# SCH_LoRaRice_Gateway__2024-06-10.net
KiCad netlist of a schematic drawn in EasyEDA
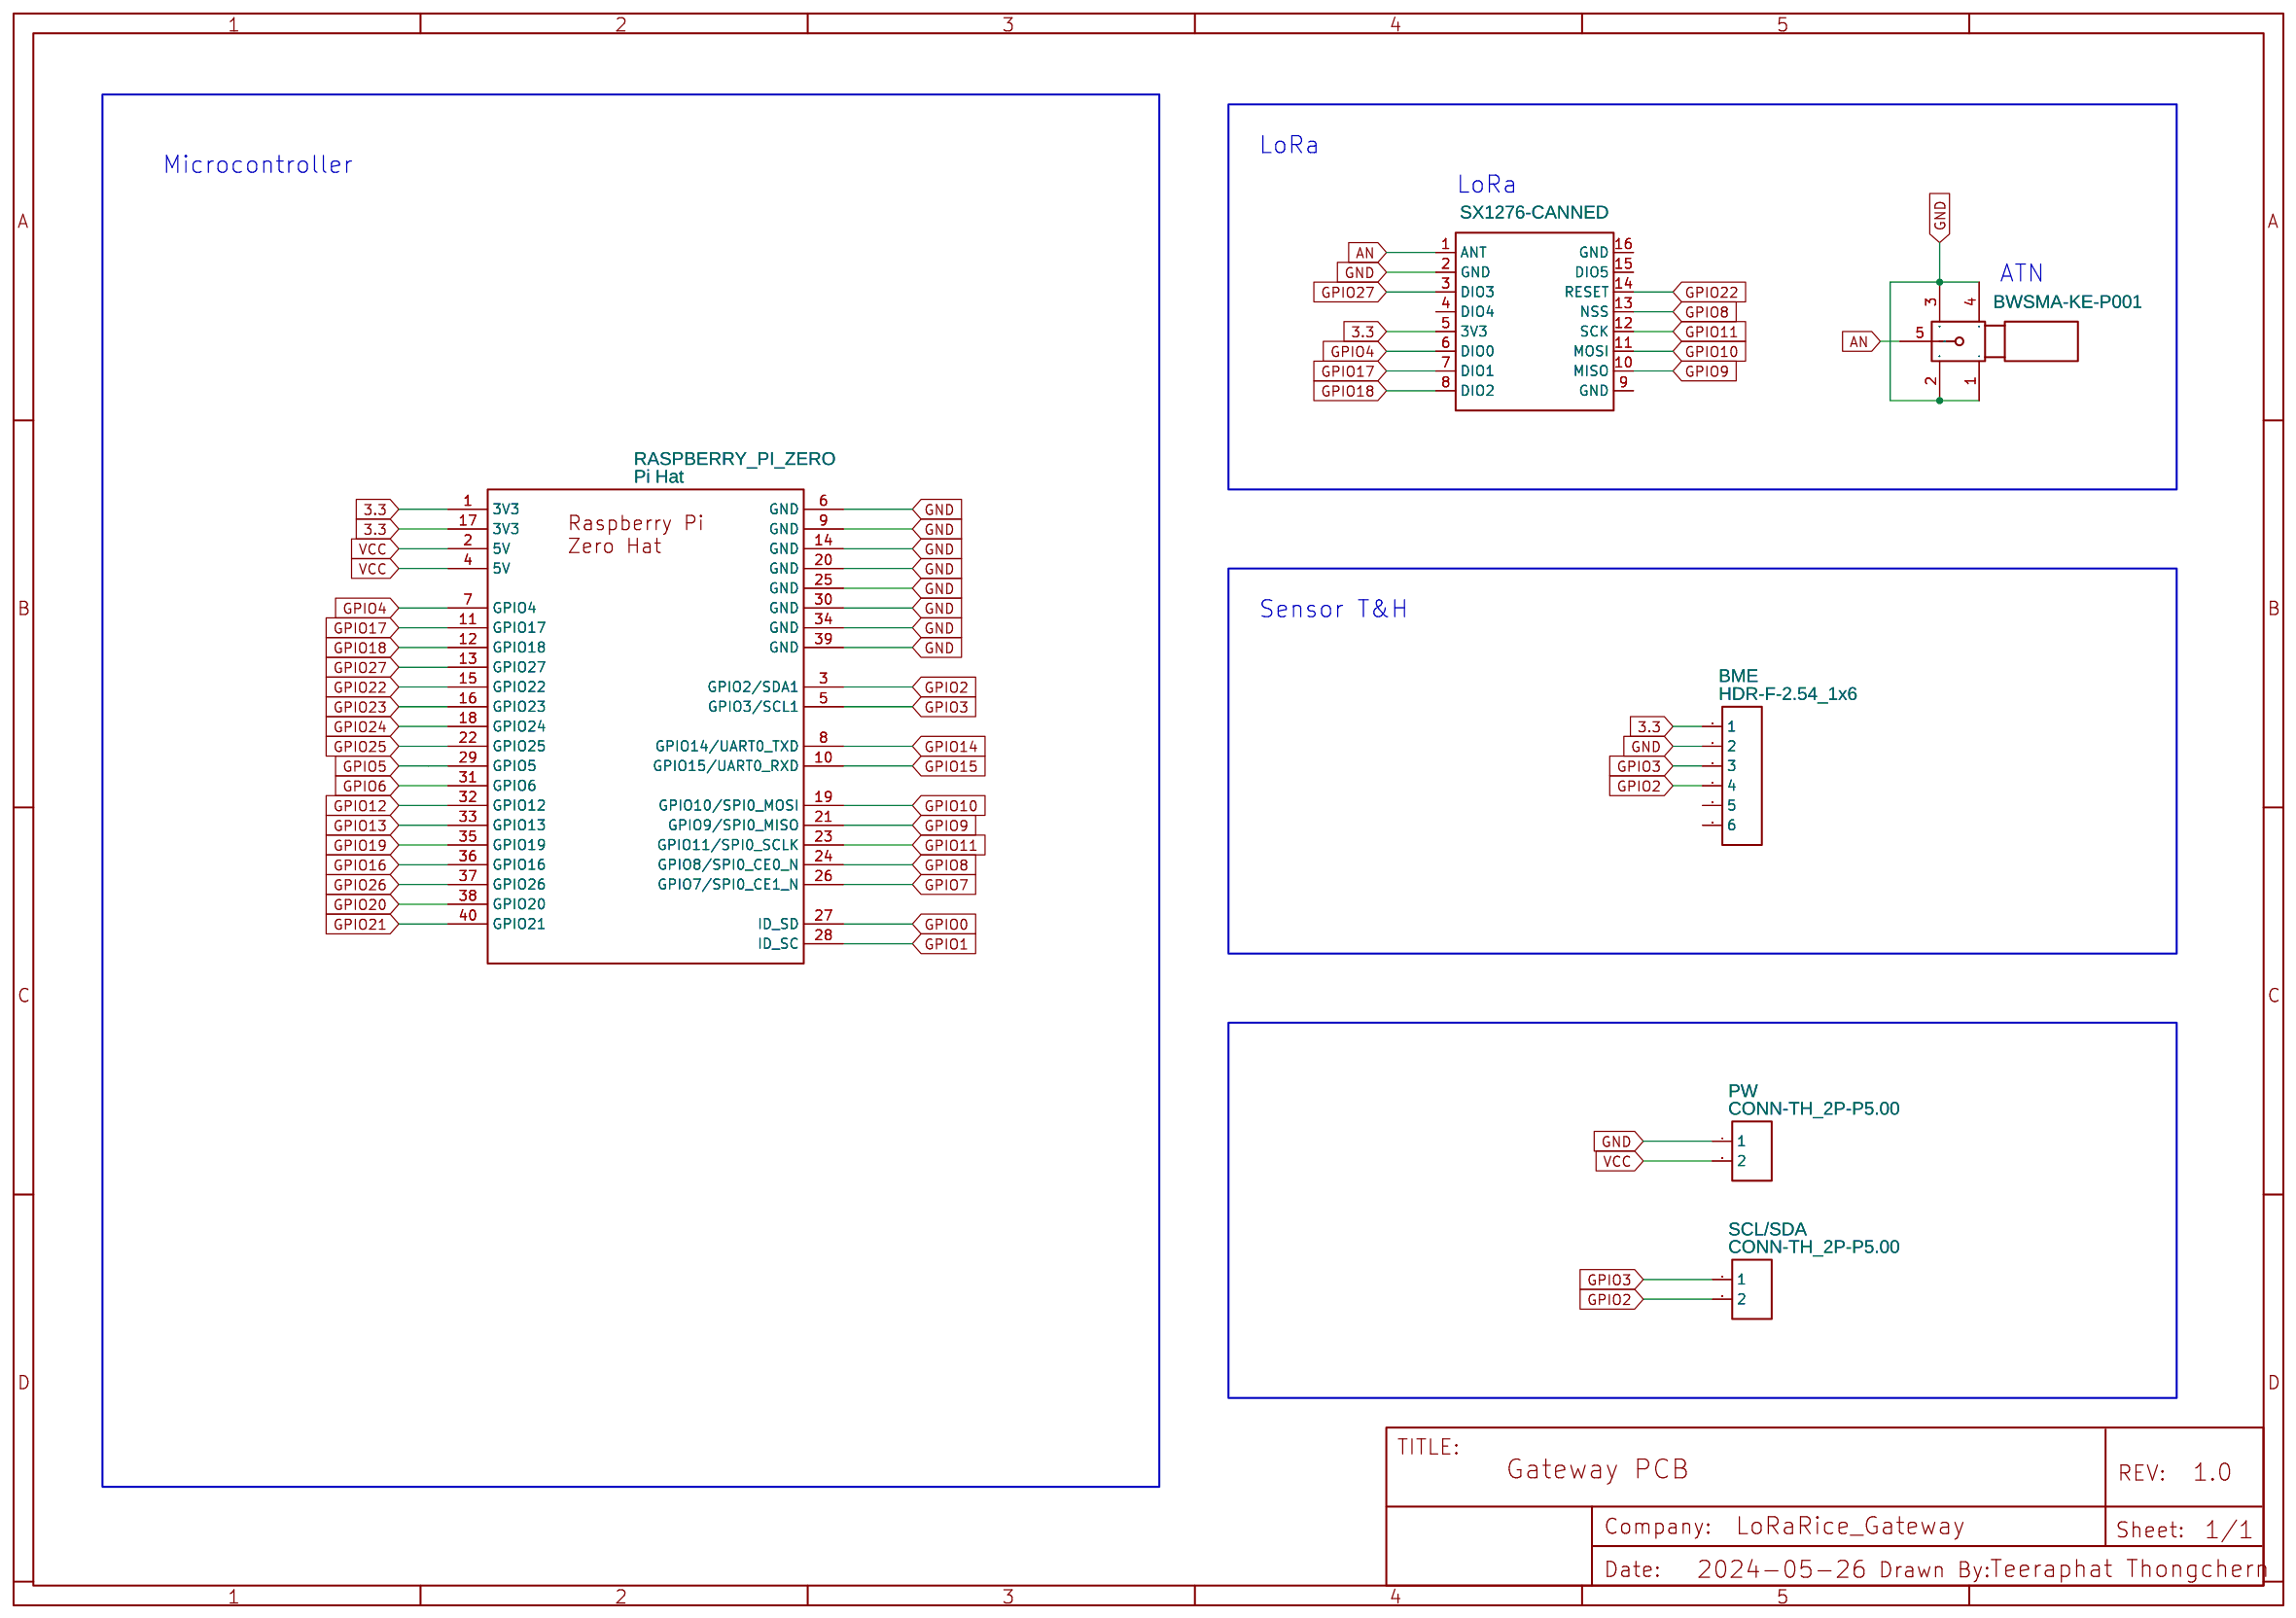
[diagram p0: schematic sheet]

(export (version "E")
  (design (tool "Eeschema 10.0.6"))
  (components
    (comp (ref "ATN")
      (value "BWSMA-KE-P001")
      (fields (field (name "Manufacturer") "BAT WIRELESS(蝙蝠无线)"))
      (libsource (lib "") (part "BWSMA-KE-P001"))
    )
    (comp (ref "BME") (value "HDR-F-2.54_1x6") (libsource (lib "") (part "HDR-F-2.54_1x6")))
    (comp (ref "LORA")
      (value "SX1276-CANNED")
      (fields (field (name "Manufacturer Part") "LoRa1276-C1") (field (name "Manufacturer") "G-NiceRF"))
      (libsource (lib "") (part "SX1276-CANNED"))
    )
    (comp (ref "PW") (value "CONN-TH_2P-P5.00") (libsource (lib "") (part "CONN-TH_2P-P5.00_1")))
    (comp (ref "RASPBERRY_PI_ZERO")
      (value "Pi Hat")
      (fields (field (name "Manufacturer") "Raspberry Pi Foundation"))
      (libsource (lib "") (part "RPI ZERO 2W"))
    )
    (comp (ref "SCL/SDA") (value "CONN-TH_2P-P5.00") (libsource (lib "") (part "CONN-TH_2P-P5.00")))
  )
  (nets
    (net (code "1") (name "3.3") (class "Default")
      (node (ref "BME") (pin "1") (pinfunction "1_1") (pintype "input"))
      (node (ref "LORA") (pin "5") (pinfunction "3V3_5") (pintype "unspecified"))
      (node (ref "RASPBERRY_PI_ZERO") (pin "1") (pinfunction "3V3_1") (pintype "unspecified"))
      (node (ref "RASPBERRY_PI_ZERO") (pin "17") (pinfunction "3V3_17") (pintype "unspecified"))
    )
    (net (code "2") (name "AN") (class "Default")
      (node (ref "ATN") (pin "5") (pinfunction "5_5") (pintype "unspecified"))
      (node (ref "LORA") (pin "1") (pinfunction "ANT_1") (pintype "unspecified"))
    )
    (net (code "3") (name "GND") (class "Default")
      (node (ref "ATN") (pin "1") (pinfunction "1_1") (pintype "unspecified"))
      (node (ref "ATN") (pin "2") (pinfunction "2_2") (pintype "unspecified"))
      (node (ref "ATN") (pin "3") (pinfunction "3_3") (pintype "unspecified"))
      (node (ref "ATN") (pin "4") (pinfunction "4_4") (pintype "unspecified"))
      (node (ref "BME") (pin "2") (pinfunction "2_2") (pintype "input"))
      (node (ref "LORA") (pin "2") (pinfunction "GND_2") (pintype "unspecified"))
      (node (ref "PW") (pin "1") (pinfunction "1_1") (pintype "unspecified"))
      (node (ref "RASPBERRY_PI_ZERO") (pin "14") (pinfunction "GND_14") (pintype "unspecified"))
      (node (ref "RASPBERRY_PI_ZERO") (pin "20") (pinfunction "GND_20") (pintype "unspecified"))
      (node (ref "RASPBERRY_PI_ZERO") (pin "25") (pinfunction "GND_25") (pintype "unspecified"))
      (node (ref "RASPBERRY_PI_ZERO") (pin "30") (pinfunction "GND_30") (pintype "unspecified"))
      (node (ref "RASPBERRY_PI_ZERO") (pin "34") (pinfunction "GND_34") (pintype "unspecified"))
      (node (ref "RASPBERRY_PI_ZERO") (pin "39") (pinfunction "GND_39") (pintype "unspecified"))
      (node (ref "RASPBERRY_PI_ZERO") (pin "6") (pinfunction "GND_6") (pintype "unspecified"))
      (node (ref "RASPBERRY_PI_ZERO") (pin "9") (pinfunction "GND_9") (pintype "unspecified"))
    )
    (net (code "4") (name "GPIO0") (class "Default")
      (node (ref "RASPBERRY_PI_ZERO") (pin "27") (pinfunction "ID_SD_27") (pintype "unspecified"))
    )
    (net (code "5") (name "GPIO1") (class "Default")
      (node (ref "RASPBERRY_PI_ZERO") (pin "28") (pinfunction "ID_SC_28") (pintype "unspecified"))
    )
    (net (code "6") (name "GPIO2") (class "Default")
      (node (ref "BME") (pin "4") (pinfunction "4_4") (pintype "input"))
      (node (ref "RASPBERRY_PI_ZERO") (pin "3") (pinfunction "GPIO2/SDA1_3") (pintype "unspecified"))
      (node (ref "SCL/SDA") (pin "2") (pinfunction "2_2") (pintype "unspecified"))
    )
    (net (code "7") (name "GPIO3") (class "Default")
      (node (ref "BME") (pin "3") (pinfunction "3_3") (pintype "input"))
      (node (ref "RASPBERRY_PI_ZERO") (pin "5") (pinfunction "GPIO3/SCL1_5") (pintype "unspecified"))
      (node (ref "SCL/SDA") (pin "1") (pinfunction "1_1") (pintype "unspecified"))
    )
    (net (code "8") (name "GPIO4") (class "Default")
      (node (ref "LORA") (pin "6") (pinfunction "DIO0_6") (pintype "unspecified"))
      (node (ref "RASPBERRY_PI_ZERO") (pin "7") (pinfunction "GPIO4_7") (pintype "unspecified"))
    )
    (net (code "9") (name "GPIO5") (class "Default")
      (node (ref "RASPBERRY_PI_ZERO") (pin "29") (pinfunction "GPIO5_29") (pintype "unspecified"))
    )
    (net (code "10") (name "GPIO6") (class "Default")
      (node (ref "RASPBERRY_PI_ZERO") (pin "31") (pinfunction "GPIO6_31") (pintype "unspecified"))
    )
    (net (code "11") (name "GPIO7") (class "Default")
      (node (ref "RASPBERRY_PI_ZERO") (pin "26") (pinfunction "GPIO7/SPI0_CE1_N_26") (pintype "unspecified"))
    )
    (net (code "12") (name "GPIO8") (class "Default")
      (node (ref "LORA") (pin "13") (pinfunction "NSS_13") (pintype "unspecified"))
      (node (ref "RASPBERRY_PI_ZERO") (pin "24") (pinfunction "GPIO8/SPI0_CE0_N_24") (pintype "unspecified"))
    )
    (net (code "13") (name "GPIO9") (class "Default")
      (node (ref "LORA") (pin "10") (pinfunction "MISO_10") (pintype "unspecified"))
      (node (ref "RASPBERRY_PI_ZERO") (pin "21") (pinfunction "GPIO9/SPI0_MISO_21") (pintype "unspecified"))
    )
    (net (code "14") (name "GPIO10") (class "Default")
      (node (ref "LORA") (pin "11") (pinfunction "MOSI_11") (pintype "unspecified"))
      (node (ref "RASPBERRY_PI_ZERO") (pin "19") (pinfunction "GPIO10/SPI0_MOSI_19") (pintype "unspecified"))
    )
    (net (code "15") (name "GPIO11") (class "Default")
      (node (ref "LORA") (pin "12") (pinfunction "SCK_12") (pintype "unspecified"))
      (node (ref "RASPBERRY_PI_ZERO") (pin "23") (pinfunction "GPIO11/SPI0_SCLK_23") (pintype "unspecified"))
    )
    (net (code "16") (name "GPIO12") (class "Default")
      (node (ref "RASPBERRY_PI_ZERO") (pin "32") (pinfunction "GPIO12_32") (pintype "unspecified"))
    )
    (net (code "17") (name "GPIO13") (class "Default")
      (node (ref "RASPBERRY_PI_ZERO") (pin "33") (pinfunction "GPIO13_33") (pintype "unspecified"))
    )
    (net (code "18") (name "GPIO14") (class "Default")
      (node (ref "RASPBERRY_PI_ZERO") (pin "8") (pinfunction "GPIO14/UART0_TXD_8") (pintype "unspecified"))
    )
    (net (code "19") (name "GPIO15") (class "Default")
      (node (ref "RASPBERRY_PI_ZERO") (pin "10") (pinfunction "GPIO15/UART0_RXD_10") (pintype "unspecified"))
    )
    (net (code "20") (name "GPIO16") (class "Default")
      (node (ref "RASPBERRY_PI_ZERO") (pin "36") (pinfunction "GPIO16_36") (pintype "unspecified"))
    )
    (net (code "21") (name "GPIO17") (class "Default")
      (node (ref "LORA") (pin "7") (pinfunction "DIO1_7") (pintype "unspecified"))
      (node (ref "RASPBERRY_PI_ZERO") (pin "11") (pinfunction "GPIO17_11") (pintype "unspecified"))
    )
    (net (code "22") (name "GPIO18") (class "Default")
      (node (ref "LORA") (pin "8") (pinfunction "DIO2_8") (pintype "unspecified"))
      (node (ref "RASPBERRY_PI_ZERO") (pin "12") (pinfunction "GPIO18_12") (pintype "unspecified"))
    )
    (net (code "23") (name "GPIO19") (class "Default")
      (node (ref "RASPBERRY_PI_ZERO") (pin "35") (pinfunction "GPIO19_35") (pintype "unspecified"))
    )
    (net (code "24") (name "GPIO20") (class "Default")
      (node (ref "RASPBERRY_PI_ZERO") (pin "38") (pinfunction "GPIO20_38") (pintype "unspecified"))
    )
    (net (code "25") (name "GPIO21") (class "Default")
      (node (ref "RASPBERRY_PI_ZERO") (pin "40") (pinfunction "GPIO21_40") (pintype "unspecified"))
    )
    (net (code "26") (name "GPIO22") (class "Default")
      (node (ref "LORA") (pin "14") (pinfunction "RESET_14") (pintype "unspecified"))
      (node (ref "RASPBERRY_PI_ZERO") (pin "15") (pinfunction "GPIO22_15") (pintype "unspecified"))
    )
    (net (code "27") (name "GPIO23") (class "Default")
      (node (ref "RASPBERRY_PI_ZERO") (pin "16") (pinfunction "GPIO23_16") (pintype "unspecified"))
    )
    (net (code "28") (name "GPIO24") (class "Default")
      (node (ref "RASPBERRY_PI_ZERO") (pin "18") (pinfunction "GPIO24_18") (pintype "unspecified"))
    )
    (net (code "29") (name "GPIO25") (class "Default")
      (node (ref "RASPBERRY_PI_ZERO") (pin "22") (pinfunction "GPIO25_22") (pintype "unspecified"))
    )
    (net (code "30") (name "GPIO26") (class "Default")
      (node (ref "RASPBERRY_PI_ZERO") (pin "37") (pinfunction "GPIO26_37") (pintype "unspecified"))
    )
    (net (code "31") (name "GPIO27") (class "Default")
      (node (ref "LORA") (pin "3") (pinfunction "DIO3_3") (pintype "unspecified"))
      (node (ref "RASPBERRY_PI_ZERO") (pin "13") (pinfunction "GPIO27_13") (pintype "unspecified"))
    )
    (net (code "32") (name "VCC") (class "Default")
      (node (ref "PW") (pin "2") (pinfunction "2_2") (pintype "unspecified"))
      (node (ref "RASPBERRY_PI_ZERO") (pin "2") (pinfunction "5V_2") (pintype "unspecified"))
      (node (ref "RASPBERRY_PI_ZERO") (pin "4") (pinfunction "5V_4") (pintype "unspecified"))
    )
    (net (code "33") (name "unconnected-(BME-Pad5)") (class "Default")
      (node (ref "BME") (pin "5") (pinfunction "5_5") (pintype "input"))
    )
    (net (code "34") (name "unconnected-(BME-Pad6)") (class "Default")
      (node (ref "BME") (pin "6") (pinfunction "6_6") (pintype "input"))
    )
    (net (code "35") (name "unconnected-(LORA-DIO4-Pad4)") (class "Default")
      (node (ref "LORA") (pin "4") (pinfunction "DIO4_4") (pintype "unspecified"))
    )
    (net (code "36") (name "unconnected-(LORA-DIO5-Pad15)") (class "Default")
      (node (ref "LORA") (pin "15") (pinfunction "DIO5_15") (pintype "unspecified"))
    )
    (net (code "37") (name "unconnected-(LORA-GND-Pad9)") (class "Default")
      (node (ref "LORA") (pin "9") (pinfunction "GND_9") (pintype "unspecified"))
    )
    (net (code "38") (name "unconnected-(LORA-GND-Pad16)") (class "Default")
      (node (ref "LORA") (pin "16") (pinfunction "GND_16") (pintype "unspecified"))
    )
  )
)
